# Sheet1.net
KiCad netlist of a schematic drawn in Altium Designer
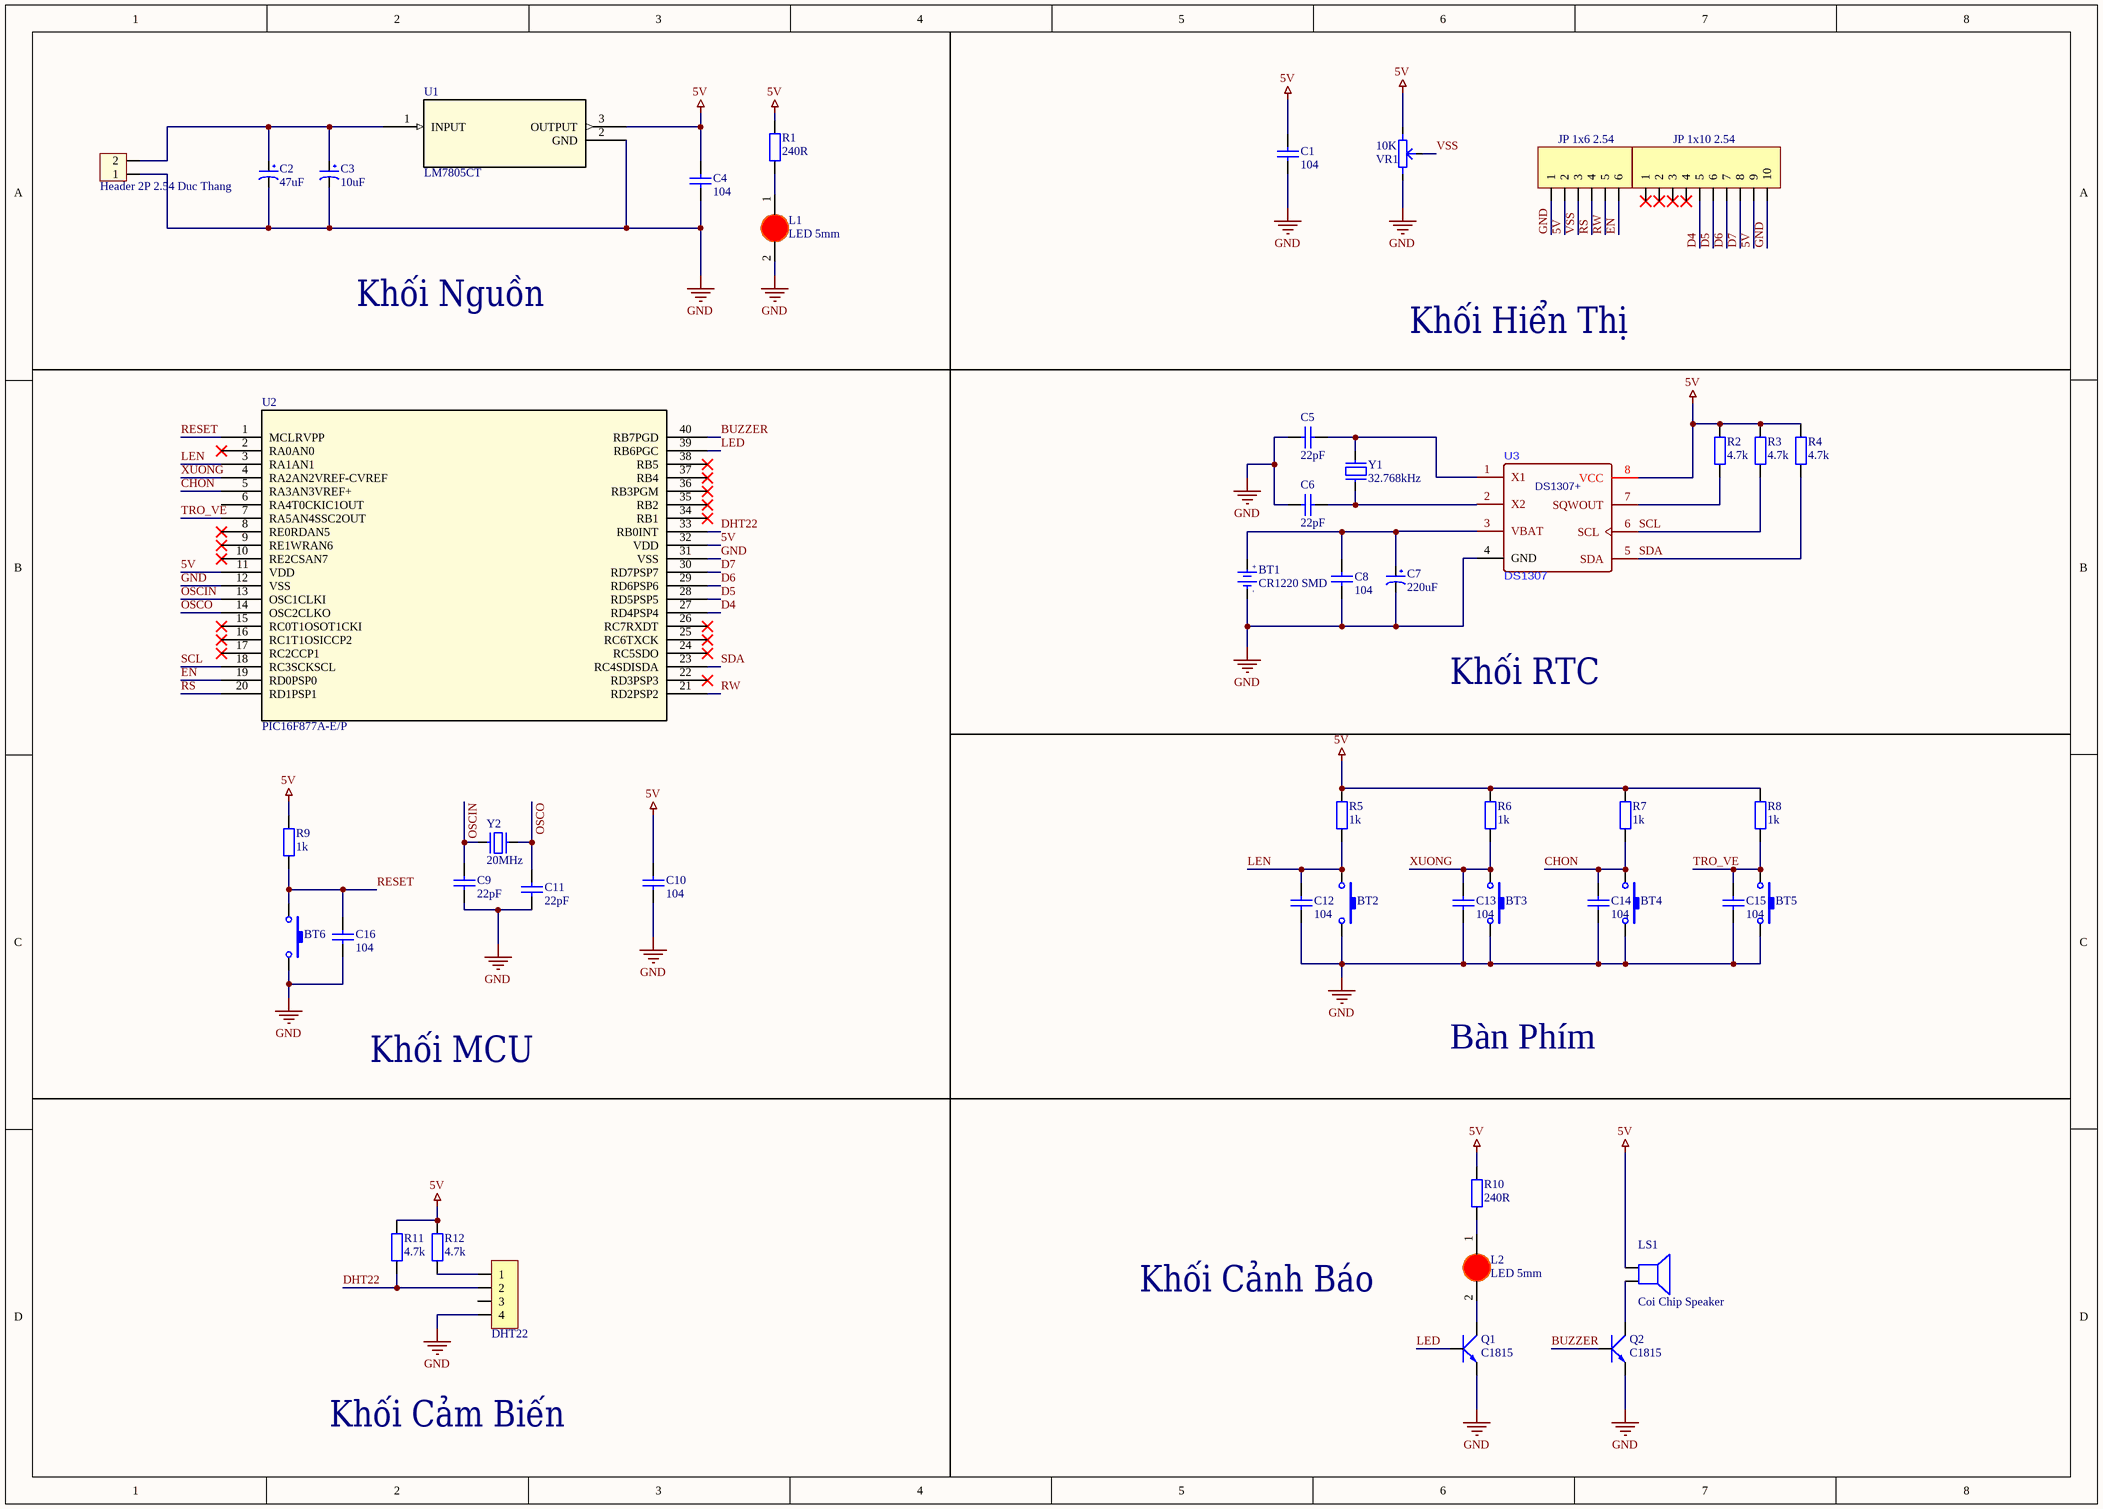
[diagram p0: Sheet1.SchDoc]

(export (version "E")
  (design (tool "Eeschema 10.0.6"))
  (components
    (comp (ref "BT1")
      (value "CR1220 SMD")
      (footprint "DE PIN CR1220")
      (libsource (lib "Altium_Lib_by_KhueNguyenCreator") (part "De pin CR1220 SMD"))
    )
    (comp (ref "BT2")
      (value "Nut Nhan 2 Chan SMD 3x6x2.5")
      (footprint "Nut Nhan 2 Chan SMD 3x6x2.5")
      (libsource (lib "Altium_Lib_by_KhueNguyenCreator") (part "Nut Nhan 2 Chan SMD 3x6x2.5"))
    )
    (comp (ref "BT3")
      (value "Nut Nhan 2 Chan SMD 3x6x2.5")
      (footprint "Nut Nhan 2 Chan SMD 3x6x2.5")
      (libsource (lib "Altium_Lib_by_KhueNguyenCreator") (part "Nut Nhan 2 Chan SMD 3x6x2.5"))
    )
    (comp (ref "BT4")
      (value "Nut Nhan 2 Chan SMD 3x6x2.5")
      (footprint "Nut Nhan 2 Chan SMD 3x6x2.5")
      (libsource (lib "Altium_Lib_by_KhueNguyenCreator") (part "Nut Nhan 2 Chan SMD 3x6x2.5"))
    )
    (comp (ref "BT5")
      (value "Nut Nhan 2 Chan SMD 3x6x2.5")
      (footprint "Nut Nhan 2 Chan SMD 3x6x2.5")
      (libsource (lib "Altium_Lib_by_KhueNguyenCreator") (part "Nut Nhan 2 Chan SMD 3x6x2.5"))
    )
    (comp (ref "BT6")
      (value "Nut Nhan 2 Chan SMD 3x6x2.5")
      (footprint "Nut Nhan 2 Chan SMD 3x6x2.5")
      (libsource (lib "Altium_Lib_by_KhueNguyenCreator") (part "Nut Nhan 2 Chan SMD 3x6x2.5"))
    )
    (comp (ref "C1")
      (value "104")
      (footprint "tu gom")
      (description "Cắm")
      (libsource (lib "Altium_Lib_by_KhueNguyenCreator") (part "Tu gom 104 50V"))
    )
    (comp (ref "C2")
      (value "47uF")
      (footprint "tu hoa 5mm")
      (description "Cắm")
      (libsource (lib "Altium_Lib_by_KhueNguyenCreator") (part "Tu Hoa 47uF 25V 5x8"))
    )
    (comp (ref "C3")
      (value "10uF")
      (footprint "tu hoa 4mm")
      (description "Cắm")
      (libsource (lib "Altium_Lib_by_KhueNguyenCreator") (part "Tu Hoa 10uF 25V 4x7"))
    )
    (comp (ref "C4")
      (value "104")
      (footprint "tu gom")
      (description "Cắm")
      (libsource (lib "Altium_Lib_by_KhueNguyenCreator") (part "Tu gom 104 50V"))
    )
    (comp (ref "C5")
      (value "22pF")
      (footprint "tu gom")
      (description "Cắm")
      (libsource (lib "Altium_Lib_by_KhueNguyenCreator") (part "Tu gom 22pF 50V"))
    )
    (comp (ref "C6")
      (value "22pF")
      (footprint "tu gom")
      (description "Cắm")
      (libsource (lib "Altium_Lib_by_KhueNguyenCreator") (part "Tu gom 22pF 50V"))
    )
    (comp (ref "C7")
      (value "220uF")
      (footprint "tu hoa 5mm")
      (description "Cắm")
      (libsource (lib "Altium_Lib_by_KhueNguyenCreator") (part "Tu Hoa 220uF 10V 6x11"))
    )
    (comp (ref "C8")
      (value "104")
      (footprint "tu gom")
      (description "Cắm")
      (libsource (lib "Altium_Lib_by_KhueNguyenCreator") (part "Tu gom 104 50V"))
    )
    (comp (ref "C9")
      (value "22pF")
      (footprint "tu gom")
      (description "Cắm")
      (libsource (lib "Altium_Lib_by_KhueNguyenCreator") (part "Tu gom 22pF 50V"))
    )
    (comp (ref "C10")
      (value "104")
      (footprint "tu gom")
      (description "Cắm")
      (libsource (lib "Altium_Lib_by_KhueNguyenCreator") (part "Tu gom 104 50V"))
    )
    (comp (ref "C11")
      (value "22pF")
      (footprint "tu gom")
      (description "Cắm")
      (libsource (lib "Altium_Lib_by_KhueNguyenCreator") (part "Tu gom 22pF 50V"))
    )
    (comp (ref "C12")
      (value "104")
      (footprint "tu gom")
      (description "Cắm")
      (libsource (lib "Altium_Lib_by_KhueNguyenCreator") (part "Tu gom 104 50V"))
    )
    (comp (ref "C13")
      (value "104")
      (footprint "tu gom")
      (description "Cắm")
      (libsource (lib "Altium_Lib_by_KhueNguyenCreator") (part "Tu gom 104 50V"))
    )
    (comp (ref "C14")
      (value "104")
      (footprint "tu gom")
      (description "Cắm")
      (libsource (lib "Altium_Lib_by_KhueNguyenCreator") (part "Tu gom 104 50V"))
    )
    (comp (ref "C15")
      (value "104")
      (footprint "tu gom")
      (description "Cắm")
      (libsource (lib "Altium_Lib_by_KhueNguyenCreator") (part "Tu gom 104 50V"))
    )
    (comp (ref "C16")
      (value "104")
      (footprint "tu gom")
      (description "Cắm")
      (libsource (lib "Altium_Lib_by_KhueNguyenCreator") (part "Tu gom 104 50V"))
    )
    (comp (ref "H1")
      (value "Header 2P 2.54 Duc Thang")
      (footprint "XH2.54M-2")
      (description "Cắm")
      (libsource (lib "Altium_Lib_by_KhueNguyenCreator") (part "Header 2P 2.54 Duc Thang"))
    )
    (comp (ref "JP1")
      (value "JP 1x6 2.54")
      (footprint "JP 1x6 CT")
      (description "Cắm")
      (libsource (lib "Altium_Lib_by_KhueNguyenCreator") (part "JP 1x6 2.54 Cai Thang"))
    )
    (comp (ref "JP2")
      (value "JP 1x10 2.54")
      (footprint "JP 1x10 CT")
      (description "Cắm")
      (libsource (lib "Altium_Lib_by_KhueNguyenCreator") (part "JP 1x10 2.54 Cai Thang"))
    )
    (comp (ref "JP3")
      (value "DHT22")
      (footprint "JP 1x4 CT")
      (description "Cắm")
      (libsource (lib "Altium_Lib_by_KhueNguyenCreator") (part "JP 1x4 2.54 Cai Thang"))
    )
    (comp (ref "L1")
      (value "LED 5mm")
      (footprint "LED-5MM-RED")
      (description "Cắm")
      (libsource (lib "Altium_Lib_by_KhueNguyenCreator") (part "LED 5mm Do"))
    )
    (comp (ref "L2")
      (value "LED 5mm")
      (footprint "LED-5MM-RED")
      (description "Cắm")
      (libsource (lib "Altium_Lib_by_KhueNguyenCreator") (part "LED 5mm Do"))
    )
    (comp (ref "LS1")
      (value "Coi Chip Speaker")
      (footprint "Coi Chip Speacker")
      (description "Còi chip")
      (libsource (lib "Altium_Lib_by_KhueNguyenCreator") (part "Coi Chip Speaker"))
    )
    (comp (ref "Q1")
      (value "C1815")
      (footprint "TO92")
      (description "NPN transistor")
      (libsource (lib "Altium_Lib_by_KhueNguyenCreator") (part "Trans C1815 DIP"))
    )
    (comp (ref "Q2")
      (value "C1815")
      (footprint "TO92")
      (description "NPN transistor")
      (libsource (lib "Altium_Lib_by_KhueNguyenCreator") (part "Trans C1815 DIP"))
    )
    (comp (ref "R1")
      (value "240R")
      (footprint "tro vach 1/2w")
      (description "Cắm")
      (libsource (lib "Altium_Lib_by_KhueNguyenCreator") (part "Tro Vach 1/2W 5% 240R"))
    )
    (comp (ref "R2")
      (value "4.7k")
      (footprint "tro vach 1/2w")
      (description "Cắm")
      (libsource (lib "Altium_Lib_by_KhueNguyenCreator") (part "Tro Vach 1/2W 5% 4.7k"))
    )
    (comp (ref "R3")
      (value "4.7k")
      (footprint "tro vach 1/2w")
      (description "Cắm")
      (libsource (lib "Altium_Lib_by_KhueNguyenCreator") (part "Tro Vach 1/2W 5% 4.7k"))
    )
    (comp (ref "R4")
      (value "4.7k")
      (footprint "tro vach 1/2w")
      (description "Cắm")
      (libsource (lib "Altium_Lib_by_KhueNguyenCreator") (part "Tro Vach 1/2W 5% 4.7k"))
    )
    (comp (ref "R5")
      (value "1k")
      (footprint "tro vach 1/2w")
      (description "Cắm")
      (libsource (lib "Altium_Lib_by_KhueNguyenCreator") (part "Tro Vach 1/2W 5% 240R"))
    )
    (comp (ref "R6")
      (value "1k")
      (footprint "tro vach 1/2w")
      (description "Cắm")
      (libsource (lib "Altium_Lib_by_KhueNguyenCreator") (part "Tro Vach 1/2W 5% 240R"))
    )
    (comp (ref "R7")
      (value "1k")
      (footprint "tro vach 1/2w")
      (description "Cắm")
      (libsource (lib "Altium_Lib_by_KhueNguyenCreator") (part "Tro Vach 1/2W 5% 240R"))
    )
    (comp (ref "R8")
      (value "1k")
      (footprint "tro vach 1/2w")
      (description "Cắm")
      (libsource (lib "Altium_Lib_by_KhueNguyenCreator") (part "Tro Vach 1/2W 5% 240R"))
    )
    (comp (ref "R9")
      (value "1k")
      (footprint "tro vach 1/2w")
      (description "Cắm")
      (libsource (lib "Altium_Lib_by_KhueNguyenCreator") (part "Tro Vach 1/2W 5% 240R"))
    )
    (comp (ref "R10")
      (value "240R")
      (footprint "tro vach 1/2w")
      (description "Cắm")
      (libsource (lib "Altium_Lib_by_KhueNguyenCreator") (part "Tro Vach 1/2W 5% 240R"))
    )
    (comp (ref "R11")
      (value "4.7k")
      (footprint "tro vach 1/2w")
      (description "Cắm")
      (libsource (lib "Altium_Lib_by_KhueNguyenCreator") (part "Tro Vach 1/2W 5% 4.7k"))
    )
    (comp (ref "R12")
      (value "4.7k")
      (footprint "tro vach 1/2w")
      (description "Cắm")
      (libsource (lib "Altium_Lib_by_KhueNguyenCreator") (part "Tro Vach 1/2W 5% 4.7k"))
    )
    (comp (ref "U1")
      (value "LM7805CT")
      (footprint "TO220-3_ONS")
      (description "No Description Available")
      (fields (field (name "COPYRIGHT") "Copyright (C) 2023 Ultra Librarian. All rights reserved."))
      (libsource (lib "LM7805CT") (part "LM7805CT"))
    )
    (comp (ref "U2")
      (value "PIC16F877A-E/P")
      (footprint "PDIP40_600MC_MCH")
      (description "No Description Available")
      (fields (field (name "COPYRIGHT") "Copyright (C) 2023 Ultra Librarian. All rights reserved."))
      (libsource (lib "PIC16F877A-EP") (part "PIC16F877A-EP"))
    )
    (comp (ref "U3")
      (value "DS1307")
      (footprint "SOP 8")
      (description "C5145427")
      (libsource (lib "Altium_Lib_by_KhueNguyenCreator") (part "DS1307"))
    )
    (comp (ref "VR1")
      (value "10K")
      (footprint "Bien Tro Tam Giac Dung")
      (description "Cắm")
      (libsource (lib "Altium_Lib_by_KhueNguyenCreator") (part "Bien tro tam giac 10K Dung"))
    )
    (comp (ref "Y1")
      (value "32.768kHz")
      (footprint "Thach Anh 2 Chan 32,768 KHz")
      (description "Crystal For all Crystal 2pin.")
      (libsource (lib "Altium_Lib_by_KhueNguyenCreator") (part "Thach Anh 2 chan 32,768 Khz"))
    )
    (comp (ref "Y2")
      (value "20MHz")
      (footprint "Thach Anh 2 chan cam")
      (description "Crystal For all Crystal 2pin.")
      (libsource (lib "Altium_Lib_by_KhueNguyenCreator") (part "Thach Anh 2 chan Cam"))
    )
  )
  (nets
    (net (code "2") (name "/BUZZER") (class "Default")
      (node (ref "Q2") (pin "3") (pinfunction "B_3") (pintype "passive"))
      (node (ref "U2") (pin "40") (pinfunction "RB7PGD_40") (pintype "passive"))
    )
    (net (code "3") (name "/CHON") (class "Default")
      (node (ref "BT4") (pin "1") (pinfunction "1_1") (pintype "passive"))
      (node (ref "C14") (pin "1") (pinfunction "1_1") (pintype "passive"))
      (node (ref "R7") (pin "1") (pinfunction "1_1") (pintype "passive"))
      (node (ref "U2") (pin "5") (pinfunction "RA3AN3VREF+_5") (pintype "passive"))
    )
    (net (code "4") (name "/D4") (class "Default")
      (node (ref "JP2") (pin "5") (pinfunction "5_5") (pintype "passive"))
      (node (ref "U2") (pin "27") (pinfunction "RD4PSP4_27") (pintype "passive"))
    )
    (net (code "5") (name "/D5") (class "Default")
      (node (ref "JP2") (pin "6") (pinfunction "6_6") (pintype "passive"))
      (node (ref "U2") (pin "28") (pinfunction "RD5PSP5_28") (pintype "passive"))
    )
    (net (code "6") (name "/D6") (class "Default")
      (node (ref "JP2") (pin "7") (pinfunction "7_7") (pintype "passive"))
      (node (ref "U2") (pin "29") (pinfunction "RD6PSP6_29") (pintype "passive"))
    )
    (net (code "7") (name "/D7") (class "Default")
      (node (ref "JP2") (pin "8") (pinfunction "8_8") (pintype "passive"))
      (node (ref "U2") (pin "30") (pinfunction "RD7PSP7_30") (pintype "passive"))
    )
    (net (code "8") (name "/DHT22") (class "Default")
      (node (ref "JP3") (pin "2") (pinfunction "2_2") (pintype "passive"))
      (node (ref "R11") (pin "1") (pinfunction "1_1") (pintype "passive"))
      (node (ref "U2") (pin "33") (pinfunction "RB0INT_33") (pintype "passive"))
    )
    (net (code "9") (name "/EN") (class "Default")
      (node (ref "JP1") (pin "6") (pinfunction "6_6") (pintype "passive"))
      (node (ref "U2") (pin "19") (pinfunction "RD0PSP0_19") (pintype "passive"))
    )
    (net (code "10") (name "/LED") (class "Default")
      (node (ref "Q1") (pin "3") (pinfunction "B_3") (pintype "passive"))
      (node (ref "U2") (pin "39") (pinfunction "RB6PGC_39") (pintype "passive"))
    )
    (net (code "11") (name "/LEN") (class "Default")
      (node (ref "BT2") (pin "1") (pinfunction "1_1") (pintype "passive"))
      (node (ref "C12") (pin "1") (pinfunction "1_1") (pintype "passive"))
      (node (ref "R5") (pin "1") (pinfunction "1_1") (pintype "passive"))
      (node (ref "U2") (pin "3") (pinfunction "RA1AN1_3") (pintype "passive"))
    )
    (net (code "12") (name "/OSCIN") (class "Default")
      (node (ref "C9") (pin "1") (pinfunction "1_1") (pintype "passive"))
      (node (ref "U2") (pin "13") (pinfunction "OSC1CLKI_13") (pintype "passive"))
      (node (ref "Y2") (pin "1") (pinfunction "1_1") (pintype "passive"))
    )
    (net (code "13") (name "/OSCO") (class "Default")
      (node (ref "C11") (pin "1") (pinfunction "1_1") (pintype "passive"))
      (node (ref "U2") (pin "14") (pinfunction "OSC2CLKO_14") (pintype "passive"))
      (node (ref "Y2") (pin "2") (pinfunction "2_2") (pintype "passive"))
    )
    (net (code "14") (name "/RESET") (class "Default")
      (node (ref "BT6") (pin "1") (pinfunction "1_1") (pintype "passive"))
      (node (ref "C16") (pin "1") (pinfunction "1_1") (pintype "passive"))
      (node (ref "R9") (pin "1") (pinfunction "1_1") (pintype "passive"))
      (node (ref "U2") (pin "1") (pinfunction "MCLRVPP_1") (pintype "passive"))
    )
    (net (code "15") (name "/RS") (class "Default")
      (node (ref "JP1") (pin "4") (pinfunction "4_4") (pintype "passive"))
      (node (ref "U2") (pin "20") (pinfunction "RD1PSP1_20") (pintype "passive"))
    )
    (net (code "16") (name "/RW") (class "Default")
      (node (ref "JP1") (pin "5") (pinfunction "5_5") (pintype "passive"))
      (node (ref "U2") (pin "21") (pinfunction "RD2PSP2_21") (pintype "passive"))
    )
    (net (code "17") (name "/SCL") (class "Default")
      (node (ref "R3") (pin "1") (pinfunction "1_1") (pintype "passive"))
      (node (ref "U2") (pin "18") (pinfunction "RC3SCKSCL_18") (pintype "passive"))
      (node (ref "U3") (pin "6") (pinfunction "SCL_6") (pintype "passive"))
    )
    (net (code "18") (name "/SDA") (class "Default")
      (node (ref "R4") (pin "1") (pinfunction "1_1") (pintype "passive"))
      (node (ref "U2") (pin "23") (pinfunction "RC4SDISDA_23") (pintype "passive"))
      (node (ref "U3") (pin "5") (pinfunction "SDA_5") (pintype "passive"))
    )
    (net (code "19") (name "/TRO_VE") (class "Default")
      (node (ref "BT5") (pin "1") (pinfunction "1_1") (pintype "passive"))
      (node (ref "C15") (pin "1") (pinfunction "1_1") (pintype "passive"))
      (node (ref "R8") (pin "1") (pinfunction "1_1") (pintype "passive"))
      (node (ref "U2") (pin "7") (pinfunction "RA5AN4SSC2OUT_7") (pintype "passive"))
    )
    (net (code "20") (name "/VSS") (class "Default")
      (node (ref "JP1") (pin "3") (pinfunction "3_3") (pintype "passive"))
      (node (ref "VR1") (pin "2") (pinfunction "2_2") (pintype "passive"))
    )
    (net (code "21") (name "/XUONG") (class "Default")
      (node (ref "BT3") (pin "1") (pinfunction "1_1") (pintype "passive"))
      (node (ref "C13") (pin "1") (pinfunction "1_1") (pintype "passive"))
      (node (ref "R6") (pin "1") (pinfunction "1_1") (pintype "passive"))
      (node (ref "U2") (pin "4") (pinfunction "RA2AN2VREF-CVREF_4") (pintype "passive"))
    )
    (net (code "22") (name "5V") (class "Default")
      (node (ref "C1") (pin "1") (pinfunction "1_1") (pintype "passive"))
      (node (ref "C10") (pin "1") (pinfunction "1_1") (pintype "passive"))
      (node (ref "C4") (pin "1") (pinfunction "1_1") (pintype "passive"))
      (node (ref "JP1") (pin "2") (pinfunction "2_2") (pintype "passive"))
      (node (ref "JP2") (pin "9") (pinfunction "9_9") (pintype "passive"))
      (node (ref "LS1") (pin "1") (pinfunction "1_1") (pintype "passive"))
      (node (ref "R1") (pin "2") (pinfunction "2_2") (pintype "passive"))
      (node (ref "R10") (pin "2") (pinfunction "2_2") (pintype "passive"))
      (node (ref "R11") (pin "2") (pinfunction "2_2") (pintype "passive"))
      (node (ref "R12") (pin "2") (pinfunction "2_2") (pintype "passive"))
      (node (ref "R2") (pin "2") (pinfunction "2_2") (pintype "passive"))
      (node (ref "R3") (pin "2") (pinfunction "2_2") (pintype "passive"))
      (node (ref "R4") (pin "2") (pinfunction "2_2") (pintype "passive"))
      (node (ref "R5") (pin "2") (pinfunction "2_2") (pintype "passive"))
      (node (ref "R6") (pin "2") (pinfunction "2_2") (pintype "passive"))
      (node (ref "R7") (pin "2") (pinfunction "2_2") (pintype "passive"))
      (node (ref "R8") (pin "2") (pinfunction "2_2") (pintype "passive"))
      (node (ref "R9") (pin "2") (pinfunction "2_2") (pintype "passive"))
      (node (ref "U1") (pin "3") (pinfunction "OUTPUT_3") (pintype "output"))
      (node (ref "U2") (pin "11") (pinfunction "VDD_11") (pintype "passive"))
      (node (ref "U2") (pin "32") (pinfunction "VDD_32") (pintype "passive"))
      (node (ref "U3") (pin "8") (pinfunction "VCC_8") (pintype "passive"))
      (node (ref "VR1") (pin "1") (pinfunction "1_1") (pintype "passive"))
    )
    (net (code "23") (name "GND") (class "Default")
      (node (ref "BT1") (pin "2") (pinfunction "GND_2") (pintype "passive"))
      (node (ref "BT2") (pin "2") (pinfunction "2_2") (pintype "passive"))
      (node (ref "BT3") (pin "2") (pinfunction "2_2") (pintype "passive"))
      (node (ref "BT4") (pin "2") (pinfunction "2_2") (pintype "passive"))
      (node (ref "BT5") (pin "2") (pinfunction "2_2") (pintype "passive"))
      (node (ref "BT6") (pin "2") (pinfunction "2_2") (pintype "passive"))
      (node (ref "C1") (pin "2") (pinfunction "2_2") (pintype "passive"))
      (node (ref "C10") (pin "2") (pinfunction "2_2") (pintype "passive"))
      (node (ref "C11") (pin "2") (pinfunction "2_2") (pintype "passive"))
      (node (ref "C12") (pin "2") (pinfunction "2_2") (pintype "passive"))
      (node (ref "C13") (pin "2") (pinfunction "2_2") (pintype "passive"))
      (node (ref "C14") (pin "2") (pinfunction "2_2") (pintype "passive"))
      (node (ref "C15") (pin "2") (pinfunction "2_2") (pintype "passive"))
      (node (ref "C16") (pin "2") (pinfunction "2_2") (pintype "passive"))
      (node (ref "C2") (pin "2") (pinfunction "2_2") (pintype "passive"))
      (node (ref "C3") (pin "2") (pinfunction "2_2") (pintype "passive"))
      (node (ref "C4") (pin "2") (pinfunction "2_2") (pintype "passive"))
      (node (ref "C5") (pin "2") (pinfunction "2_2") (pintype "passive"))
      (node (ref "C6") (pin "2") (pinfunction "2_2") (pintype "passive"))
      (node (ref "C7") (pin "2") (pinfunction "2_2") (pintype "passive"))
      (node (ref "C8") (pin "2") (pinfunction "2_2") (pintype "passive"))
      (node (ref "C9") (pin "2") (pinfunction "2_2") (pintype "passive"))
      (node (ref "H1") (pin "1") (pinfunction "1_1") (pintype "passive"))
      (node (ref "JP1") (pin "1") (pinfunction "1_1") (pintype "passive"))
      (node (ref "JP2") (pin "10") (pinfunction "10_10") (pintype "passive"))
      (node (ref "JP3") (pin "4") (pinfunction "4_4") (pintype "passive"))
      (node (ref "L1") (pin "2") (pinfunction "K_2") (pintype "passive"))
      (node (ref "Q1") (pin "1") (pinfunction "E_1") (pintype "passive"))
      (node (ref "Q2") (pin "1") (pinfunction "E_1") (pintype "passive"))
      (node (ref "U1") (pin "2") (pinfunction "GND_2") (pintype "power_in"))
      (node (ref "U2") (pin "12") (pinfunction "VSS_12") (pintype "passive"))
      (node (ref "U2") (pin "31") (pinfunction "VSS_31") (pintype "passive"))
      (node (ref "U3") (pin "4") (pinfunction "GND_4") (pintype "passive"))
      (node (ref "VR1") (pin "3") (pinfunction "3_3") (pintype "passive"))
    )
    (net (code "24") (name "Net-(BT1-+3V)") (class "Default")
      (node (ref "BT1") (pin "1") (pinfunction "+3V_1") (pintype "passive"))
      (node (ref "C7") (pin "1") (pinfunction "1_1") (pintype "passive"))
      (node (ref "C8") (pin "1") (pinfunction "1_1") (pintype "passive"))
      (node (ref "U3") (pin "3") (pinfunction "VBAT_3") (pintype "passive"))
    )
    (net (code "25") (name "Net-(JP3-Pad1)") (class "Default")
      (node (ref "JP3") (pin "1") (pinfunction "1_1") (pintype "passive"))
      (node (ref "R12") (pin "1") (pinfunction "1_1") (pintype "passive"))
    )
    (net (code "26") (name "Net-(L1-A)") (class "Default")
      (node (ref "L1") (pin "1") (pinfunction "A_1") (pintype "passive"))
      (node (ref "R1") (pin "1") (pinfunction "1_1") (pintype "passive"))
    )
    (net (code "27") (name "Net-(L2-A)") (class "Default")
      (node (ref "L2") (pin "1") (pinfunction "A_1") (pintype "passive"))
      (node (ref "R10") (pin "1") (pinfunction "1_1") (pintype "passive"))
    )
    (net (code "28") (name "Net-(L2-K)") (class "Default")
      (node (ref "L2") (pin "2") (pinfunction "K_2") (pintype "passive"))
      (node (ref "Q1") (pin "2") (pinfunction "C_2") (pintype "passive"))
    )
    (net (code "29") (name "Net-(Q2-C)") (class "Default")
      (node (ref "LS1") (pin "2") (pinfunction "2_2") (pintype "passive"))
      (node (ref "Q2") (pin "2") (pinfunction "C_2") (pintype "passive"))
    )
    (net (code "30") (name "Net-(U1-INPUT)") (class "Default")
      (node (ref "C2") (pin "1") (pinfunction "1_1") (pintype "passive"))
      (node (ref "C3") (pin "1") (pinfunction "1_1") (pintype "passive"))
      (node (ref "H1") (pin "2") (pinfunction "2_2") (pintype "passive"))
      (node (ref "U1") (pin "1") (pinfunction "INPUT_1") (pintype "input"))
    )
    (net (code "31") (name "Net-(U3-SQWOUT)") (class "Default")
      (node (ref "R2") (pin "1") (pinfunction "1_1") (pintype "passive"))
      (node (ref "U3") (pin "7") (pinfunction "SQWOUT_7") (pintype "passive"))
    )
    (net (code "32") (name "Net-(U3-X1)") (class "Default")
      (node (ref "C5") (pin "1") (pinfunction "1_1") (pintype "passive"))
      (node (ref "U3") (pin "1") (pinfunction "X1_1") (pintype "passive"))
      (node (ref "Y1") (pin "2") (pinfunction "2_2") (pintype "passive"))
    )
    (net (code "33") (name "Net-(U3-X2)") (class "Default")
      (node (ref "C6") (pin "1") (pinfunction "1_1") (pintype "passive"))
      (node (ref "U3") (pin "2") (pinfunction "X2_2") (pintype "passive"))
      (node (ref "Y1") (pin "1") (pinfunction "1_1") (pintype "passive"))
    )
    (net (code "34") (name "unconnected-(JP2-Pad1)") (class "Default")
      (node (ref "JP2") (pin "1") (pinfunction "1_1") (pintype "passive+no_connect"))
    )
    (net (code "35") (name "unconnected-(JP2-Pad2)") (class "Default")
      (node (ref "JP2") (pin "2") (pinfunction "2_2") (pintype "passive+no_connect"))
    )
    (net (code "36") (name "unconnected-(JP2-Pad3)") (class "Default")
      (node (ref "JP2") (pin "3") (pinfunction "3_3") (pintype "passive+no_connect"))
    )
    (net (code "37") (name "unconnected-(JP2-Pad4)") (class "Default")
      (node (ref "JP2") (pin "4") (pinfunction "4_4") (pintype "passive+no_connect"))
    )
    (net (code "38") (name "unconnected-(JP3-Pad3)") (class "Default")
      (node (ref "JP3") (pin "3") (pinfunction "3_3") (pintype "passive"))
    )
    (net (code "39") (name "unconnected-(U2-RA0AN0-Pad2)") (class "Default")
      (node (ref "U2") (pin "2") (pinfunction "RA0AN0_2") (pintype "passive+no_connect"))
    )
    (net (code "40") (name "unconnected-(U2-RA4T0CKIC1OUT-Pad6)") (class "Default")
      (node (ref "U2") (pin "6") (pinfunction "RA4T0CKIC1OUT_6") (pintype "passive"))
    )
    (net (code "41") (name "unconnected-(U2-RB1-Pad34)") (class "Default")
      (node (ref "U2") (pin "34") (pinfunction "RB1_34") (pintype "passive+no_connect"))
    )
    (net (code "42") (name "unconnected-(U2-RB2-Pad35)") (class "Default")
      (node (ref "U2") (pin "35") (pinfunction "RB2_35") (pintype "passive+no_connect"))
    )
    (net (code "43") (name "unconnected-(U2-RB3PGM-Pad36)") (class "Default")
      (node (ref "U2") (pin "36") (pinfunction "RB3PGM_36") (pintype "passive+no_connect"))
    )
    (net (code "44") (name "unconnected-(U2-RB4-Pad37)") (class "Default")
      (node (ref "U2") (pin "37") (pinfunction "RB4_37") (pintype "passive+no_connect"))
    )
    (net (code "45") (name "unconnected-(U2-RB5-Pad38)") (class "Default")
      (node (ref "U2") (pin "38") (pinfunction "RB5_38") (pintype "passive+no_connect"))
    )
    (net (code "46") (name "unconnected-(U2-RC0T1OSOT1CKI-Pad15)") (class "Default")
      (node (ref "U2") (pin "15") (pinfunction "RC0T1OSOT1CKI_15") (pintype "passive+no_connect"))
    )
    (net (code "47") (name "unconnected-(U2-RC1T1OSICCP2-Pad16)") (class "Default")
      (node (ref "U2") (pin "16") (pinfunction "RC1T1OSICCP2_16") (pintype "passive+no_connect"))
    )
    (net (code "48") (name "unconnected-(U2-RC2CCP1-Pad17)") (class "Default")
      (node (ref "U2") (pin "17") (pinfunction "RC2CCP1_17") (pintype "passive+no_connect"))
    )
    (net (code "49") (name "unconnected-(U2-RC5SDO-Pad24)") (class "Default")
      (node (ref "U2") (pin "24") (pinfunction "RC5SDO_24") (pintype "passive+no_connect"))
    )
    (net (code "50") (name "unconnected-(U2-RC6TXCK-Pad25)") (class "Default")
      (node (ref "U2") (pin "25") (pinfunction "RC6TXCK_25") (pintype "passive+no_connect"))
    )
    (net (code "51") (name "unconnected-(U2-RC7RXDT-Pad26)") (class "Default")
      (node (ref "U2") (pin "26") (pinfunction "RC7RXDT_26") (pintype "passive+no_connect"))
    )
    (net (code "52") (name "unconnected-(U2-RD3PSP3-Pad22)") (class "Default")
      (node (ref "U2") (pin "22") (pinfunction "RD3PSP3_22") (pintype "passive+no_connect"))
    )
    (net (code "53") (name "unconnected-(U2-RE0RDAN5-Pad8)") (class "Default")
      (node (ref "U2") (pin "8") (pinfunction "RE0RDAN5_8") (pintype "passive+no_connect"))
    )
    (net (code "54") (name "unconnected-(U2-RE1WRAN6-Pad9)") (class "Default")
      (node (ref "U2") (pin "9") (pinfunction "RE1WRAN6_9") (pintype "passive+no_connect"))
    )
    (net (code "55") (name "unconnected-(U2-RE2CSAN7-Pad10)") (class "Default")
      (node (ref "U2") (pin "10") (pinfunction "RE2CSAN7_10") (pintype "passive+no_connect"))
    )
  )
)
